# main_ver2.net
KiCad netlist of a schematic drawn in Altium Designer
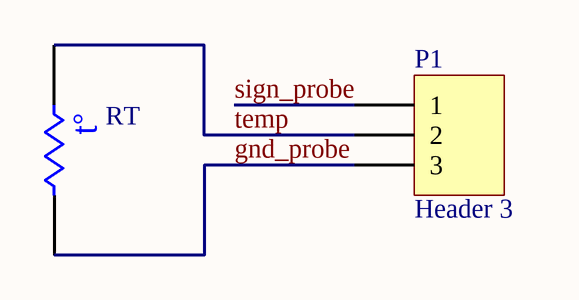
[diagram p0: main_ver2.SchDoc]

(export (version "E")
  (design (tool "Eeschema 10.0.6"))
  (components
    (comp (ref "P1")
      (value "Header 3")
      (footprint "HDR1X3")
      (description "Header, 3-Pin")
      (fields (field (name "PUBLISHER") "Altium Limited"))
      (libsource (lib "Miscellaneous Connectors") (part "Header 3"))
    )
    (comp (ref "RT")
      (value "Res Thermal")
      (footprint "6-0805_M")
      (description "Thermistor")
      (fields (field (name "PUBLISHER") "Altium Limited"))
      (libsource (lib "Miscellaneous Devices") (part "Res Thermal"))
    )
  )
  (nets
    (net (code "1") (name "/gnd_probe") (class "Default")
      (node (ref "P1") (pin "3") (pinfunction "3_3") (pintype "passive"))
      (node (ref "RT") (pin "2") (pinfunction "2_2") (pintype "passive"))
    )
    (net (code "2") (name "/sign_probe") (class "Default")
      (node (ref "P1") (pin "1") (pinfunction "1_1") (pintype "passive"))
    )
    (net (code "3") (name "/temp") (class "Default")
      (node (ref "P1") (pin "2") (pinfunction "2_2") (pintype "passive"))
      (node (ref "RT") (pin "1") (pinfunction "1_1") (pintype "passive"))
    )
  )
)
